# MEDIDOR_MTE.net
KiCad netlist of a schematic drawn in EAGLE
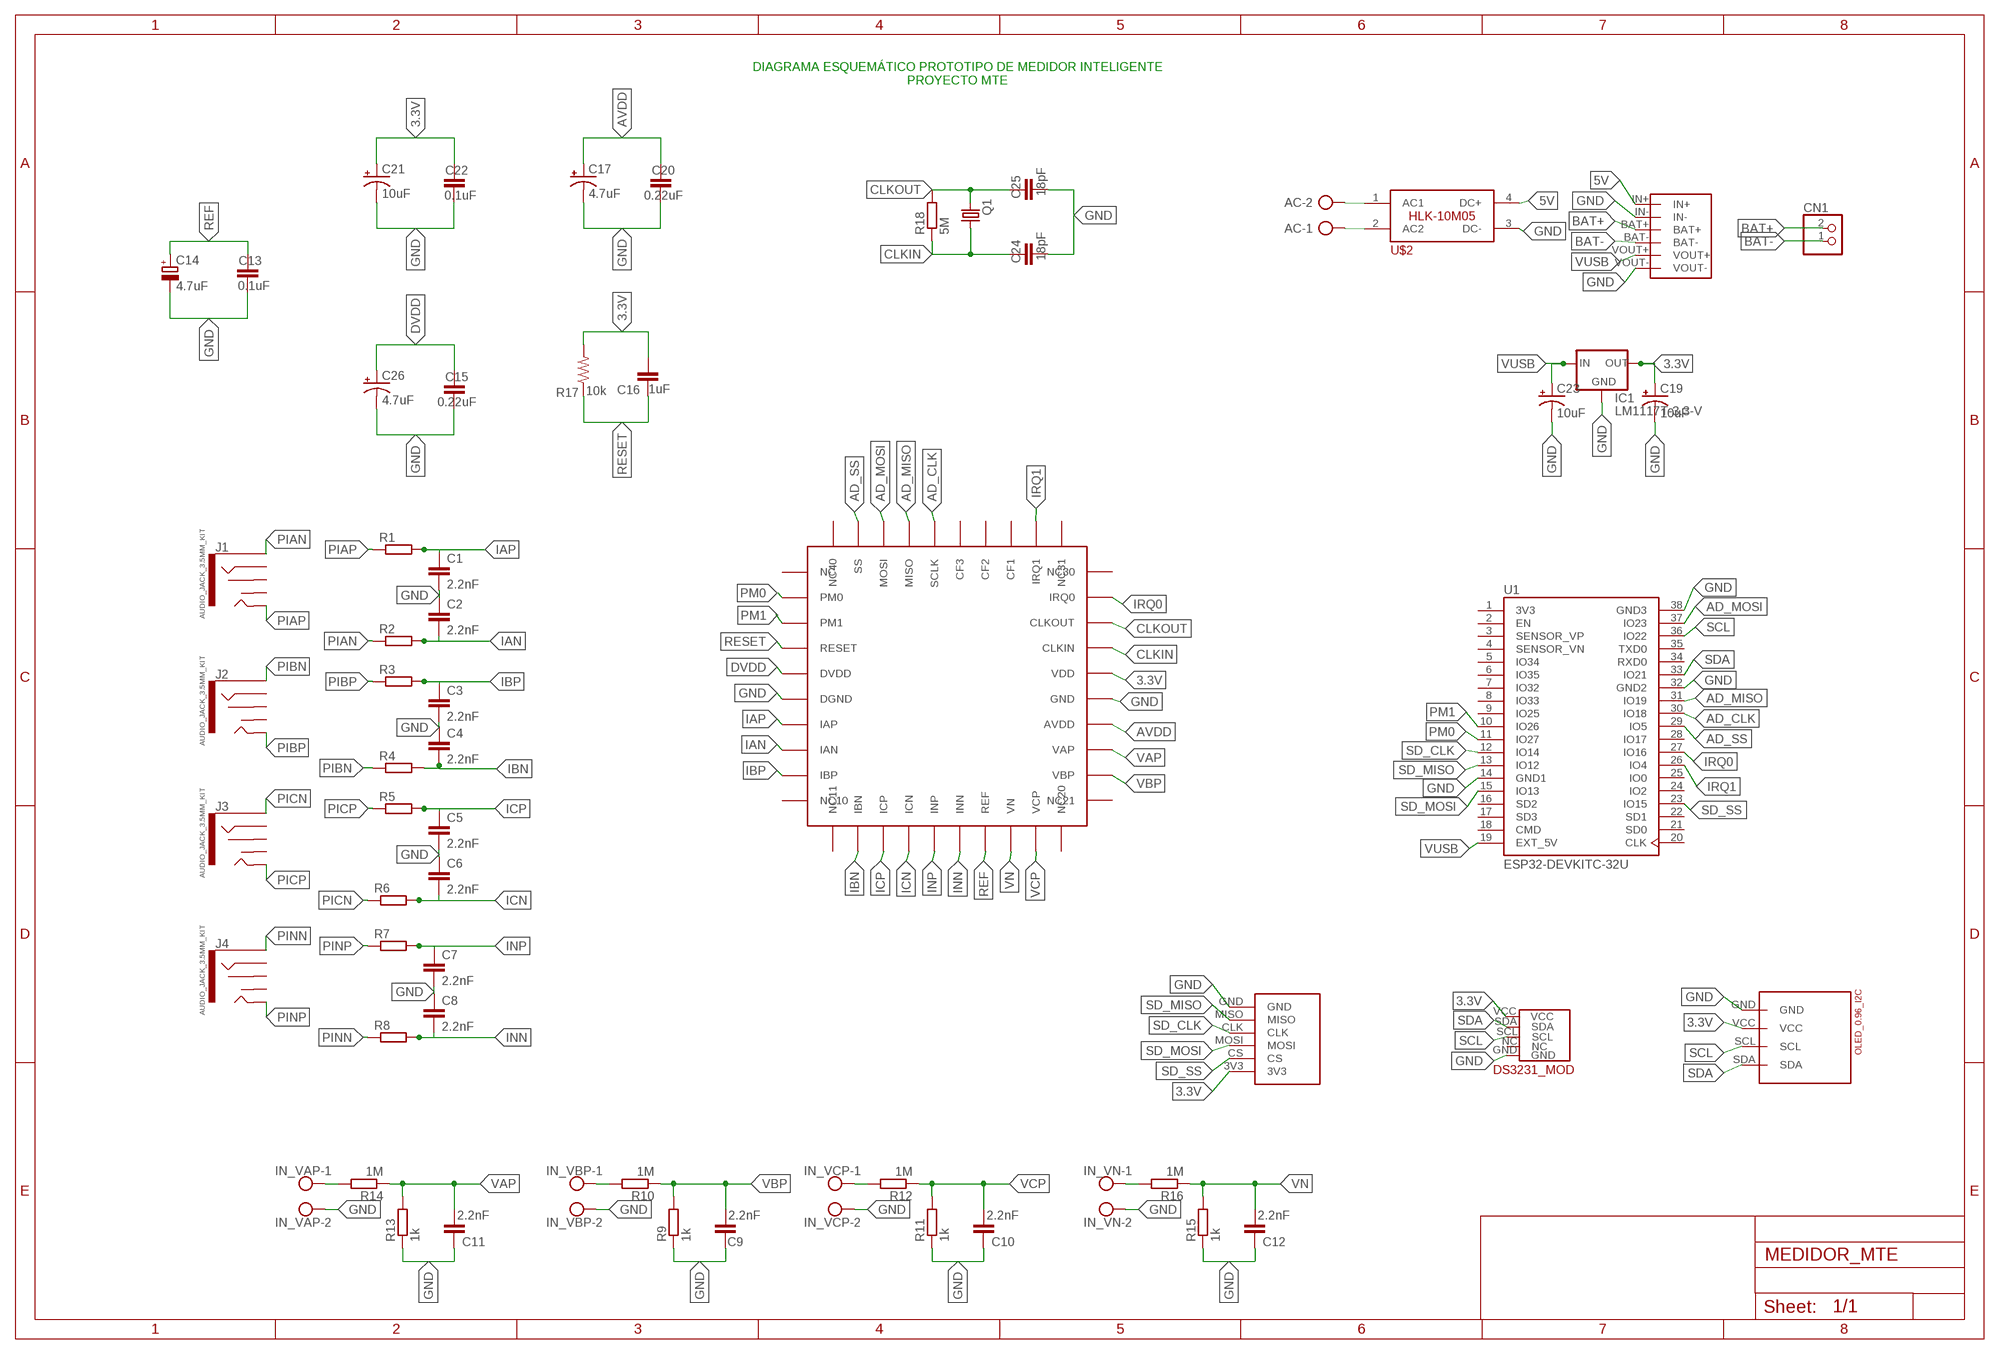
[diagram p0: schematic, sheet 1]

(export (version "E")
  (design (tool "Eeschema 10.0.6"))
  (components
    (comp (ref "AC")
      (value "AK500/2")
      (footprint "eagle-import:AK500_2")
      (libsource (lib "eagle-import") (part "AK500/2"))
    )
    (comp (ref "C1")
      (value "2.2nF")
      (footprint "eagle-import:C025-025X050")
      (libsource (lib "eagle-import") (part "C-EU025-025X050"))
    )
    (comp (ref "C2")
      (value "2.2nF")
      (footprint "eagle-import:C025-025X050")
      (libsource (lib "eagle-import") (part "C-EU025-025X050"))
    )
    (comp (ref "C3")
      (value "2.2nF")
      (footprint "eagle-import:C025-025X050")
      (libsource (lib "eagle-import") (part "C-EU025-025X050"))
    )
    (comp (ref "C4")
      (value "2.2nF")
      (footprint "eagle-import:C025-025X050")
      (libsource (lib "eagle-import") (part "C-EU025-025X050"))
    )
    (comp (ref "C5")
      (value "2.2nF")
      (footprint "eagle-import:C025-025X050")
      (libsource (lib "eagle-import") (part "C-EU025-025X050"))
    )
    (comp (ref "C6")
      (value "2.2nF")
      (footprint "eagle-import:C025-025X050")
      (libsource (lib "eagle-import") (part "C-EU025-025X050"))
    )
    (comp (ref "C7")
      (value "2.2nF")
      (footprint "eagle-import:C025-025X050")
      (libsource (lib "eagle-import") (part "C-EU025-025X050"))
    )
    (comp (ref "C8")
      (value "2.2nF")
      (footprint "eagle-import:C025-025X050")
      (libsource (lib "eagle-import") (part "C-EU025-025X050"))
    )
    (comp (ref "C9")
      (value "2.2nF")
      (footprint "eagle-import:C025-025X050")
      (libsource (lib "eagle-import") (part "C-EU025-025X050"))
    )
    (comp (ref "C10")
      (value "2.2nF")
      (footprint "eagle-import:C025-025X050")
      (libsource (lib "eagle-import") (part "C-EU025-025X050"))
    )
    (comp (ref "C11")
      (value "2.2nF")
      (footprint "eagle-import:C025-025X050")
      (libsource (lib "eagle-import") (part "C-EU025-025X050"))
    )
    (comp (ref "C12")
      (value "2.2nF")
      (footprint "eagle-import:C025-025X050")
      (libsource (lib "eagle-import") (part "C-EU025-025X050"))
    )
    (comp (ref "C13")
      (value "0.1uF")
      (footprint "eagle-import:C025-025X050")
      (libsource (lib "eagle-import") (part "C-EU025-025X050"))
    )
    (comp (ref "C14")
      (value "4.7uF")
      (footprint "eagle-import:E3,5-8")
      (libsource (lib "eagle-import") (part "CPOL-EUE3.5-8"))
    )
    (comp (ref "C15")
      (value "0.22uF")
      (footprint "eagle-import:C025-025X050")
      (libsource (lib "eagle-import") (part "C-EU025-025X050"))
    )
    (comp (ref "C16")
      (value "1uF")
      (footprint "eagle-import:C025-025X050")
      (libsource (lib "eagle-import") (part "C-EU025-025X050"))
    )
    (comp (ref "C17")
      (value "4.7uF")
      (footprint "eagle-import:E3,5-8")
      (libsource (lib "eagle-import") (part "CPOL-USE3.5-8"))
    )
    (comp (ref "C19")
      (value "10uF")
      (footprint "eagle-import:CPOL-RADIAL-2.5MM-5MM")
      (libsource (lib "eagle-import") (part "10UF-POLAR-RADIAL-2.5MM-25V-20%"))
    )
    (comp (ref "C20")
      (value "0.22uF")
      (footprint "eagle-import:C025-025X050")
      (libsource (lib "eagle-import") (part "C-EU025-025X050"))
    )
    (comp (ref "C21")
      (value "10uF")
      (footprint "eagle-import:E3,5-8")
      (libsource (lib "eagle-import") (part "CPOL-USE3.5-8"))
    )
    (comp (ref "C22")
      (value "0.1uF")
      (footprint "eagle-import:C025-025X050")
      (libsource (lib "eagle-import") (part "C-EU025-025X050"))
    )
    (comp (ref "C23")
      (value "10uF")
      (footprint "eagle-import:CPOL-RADIAL-2.5MM-5MM")
      (libsource (lib "eagle-import") (part "10UF-POLAR-RADIAL-2.5MM-25V-20%"))
    )
    (comp (ref "C24")
      (value "18pF")
      (footprint "eagle-import:C025-025X050")
      (libsource (lib "eagle-import") (part "C-EU025-025X050"))
    )
    (comp (ref "C25")
      (value "18pF")
      (footprint "eagle-import:C025-025X050")
      (libsource (lib "eagle-import") (part "C-EU025-025X050"))
    )
    (comp (ref "C26")
      (value "4.7uF")
      (footprint "eagle-import:E3,5-8")
      (libsource (lib "eagle-import") (part "CPOL-USE3.5-8"))
    )
    (comp (ref "CN1")
      (value "JST_2PIN-THM")
      (footprint "eagle-import:JST-PH-2-THM")
      (libsource (lib "eagle-import") (part "JST_2PIN-THM"))
    )
    (comp (ref "IC1")
      (value "LM1117T-3.3-V")
      (footprint "eagle-import:TO220V")
      (libsource (lib "eagle-import") (part "LM1117T--V3.3"))
    )
    (comp (ref "IN_VAP")
      (value "AK500/2")
      (footprint "eagle-import:AK500_2")
      (libsource (lib "eagle-import") (part "AK500/2"))
    )
    (comp (ref "IN_VBP")
      (value "AK500/2")
      (footprint "eagle-import:AK500_2")
      (libsource (lib "eagle-import") (part "AK500/2"))
    )
    (comp (ref "IN_VCP")
      (value "AK500/2")
      (footprint "eagle-import:AK500_2")
      (libsource (lib "eagle-import") (part "AK500/2"))
    )
    (comp (ref "IN_VN")
      (value "AK500/2")
      (footprint "eagle-import:AK500_2")
      (libsource (lib "eagle-import") (part "AK500/2"))
    )
    (comp (ref "J1")
      (value "AUDIO_JACK_3.5MM_KIT")
      (footprint "eagle-import:AUDIO-JACK-KIT")
      (libsource (lib "eagle-import") (part "AUDIO_JACK_3.5MM_KIT"))
    )
    (comp (ref "J2")
      (value "AUDIO_JACK_3.5MM_KIT")
      (footprint "eagle-import:AUDIO-JACK-KIT")
      (libsource (lib "eagle-import") (part "AUDIO_JACK_3.5MM_KIT"))
    )
    (comp (ref "J3")
      (value "AUDIO_JACK_3.5MM_KIT")
      (footprint "eagle-import:AUDIO-JACK-KIT")
      (libsource (lib "eagle-import") (part "AUDIO_JACK_3.5MM_KIT"))
    )
    (comp (ref "J4")
      (value "AUDIO_JACK_3.5MM_KIT")
      (footprint "eagle-import:AUDIO-JACK-KIT")
      (libsource (lib "eagle-import") (part "AUDIO_JACK_3.5MM_KIT"))
    )
    (comp (ref "Q1")
      (value "CRYSTALHC49S")
      (footprint "eagle-import:HC49_S")
      (libsource (lib "eagle-import") (part "CRYSTALHC49S"))
    )
    (comp (ref "R1")
      (value "R-EU_0207/12")
      (footprint "eagle-import:0207_12")
      (libsource (lib "eagle-import") (part "R-EU_0207/12"))
    )
    (comp (ref "R2")
      (value "R-EU_0207/12")
      (footprint "eagle-import:0207_12")
      (libsource (lib "eagle-import") (part "R-EU_0207/12"))
    )
    (comp (ref "R3")
      (value "R-EU_0207/12")
      (footprint "eagle-import:0207_12")
      (libsource (lib "eagle-import") (part "R-EU_0207/12"))
    )
    (comp (ref "R4")
      (value "R-EU_0207/12")
      (footprint "eagle-import:0207_12")
      (libsource (lib "eagle-import") (part "R-EU_0207/12"))
    )
    (comp (ref "R5")
      (value "R-EU_0207/12")
      (footprint "eagle-import:0207_12")
      (libsource (lib "eagle-import") (part "R-EU_0207/12"))
    )
    (comp (ref "R6")
      (value "R-EU_0207/12")
      (footprint "eagle-import:0207_12")
      (libsource (lib "eagle-import") (part "R-EU_0207/12"))
    )
    (comp (ref "R7")
      (value "R-EU_0207/12")
      (footprint "eagle-import:0207_12")
      (libsource (lib "eagle-import") (part "R-EU_0207/12"))
    )
    (comp (ref "R8")
      (value "R-EU_0207/12")
      (footprint "eagle-import:0207_12")
      (libsource (lib "eagle-import") (part "R-EU_0207/12"))
    )
    (comp (ref "R9")
      (value "1k")
      (footprint "eagle-import:0207_12")
      (libsource (lib "eagle-import") (part "rcl_v2_30891193_R-EU_0207/12"))
    )
    (comp (ref "R10")
      (value "1M")
      (footprint "eagle-import:0207_12")
      (libsource (lib "eagle-import") (part "rcl_v2_30891193_R-EU_0207/12"))
    )
    (comp (ref "R11")
      (value "1k")
      (footprint "eagle-import:0207_12")
      (libsource (lib "eagle-import") (part "rcl_v2_30891193_R-EU_0207/12"))
    )
    (comp (ref "R12")
      (value "1M")
      (footprint "eagle-import:0207_12")
      (libsource (lib "eagle-import") (part "rcl_v2_30891193_R-EU_0207/12"))
    )
    (comp (ref "R13")
      (value "1k")
      (footprint "eagle-import:0207_12")
      (libsource (lib "eagle-import") (part "rcl_v2_30891193_R-EU_0207/12"))
    )
    (comp (ref "R14")
      (value "1M")
      (footprint "eagle-import:0207_12")
      (libsource (lib "eagle-import") (part "rcl_v2_30891193_R-EU_0207/12"))
    )
    (comp (ref "R15")
      (value "1k")
      (footprint "eagle-import:0207_12")
      (libsource (lib "eagle-import") (part "rcl_v2_30891193_R-EU_0207/12"))
    )
    (comp (ref "R16")
      (value "1M")
      (footprint "eagle-import:0207_12")
      (libsource (lib "eagle-import") (part "rcl_v2_30891193_R-EU_0207/12"))
    )
    (comp (ref "R17")
      (value "10k")
      (footprint "eagle-import:0207_12")
      (libsource (lib "eagle-import") (part "R-US_0207/12"))
    )
    (comp (ref "R18")
      (value "5M")
      (footprint "eagle-import:0207_12")
      (libsource (lib "eagle-import") (part "rcl_v2_30891193_R-EU_0207/12"))
    )
    (comp (ref "U$2")
      (value "HLK-10M05")
      (footprint "eagle-import:HLK-10M05")
      (fields (field (name "MF") "Hi-link") (field (name "MP") "hlk-pm01"))
      (libsource (lib "eagle-import") (part "HLK-10M05"))
    )
    (comp (ref "U$3")
      (value "J5019_UPS")
      (footprint "eagle-import:J5019_UPS")
      (libsource (lib "eagle-import") (part "J5019_UPS"))
    )
    (comp (ref "U$4")
      (value "OLED_I2C_096")
      (footprint "eagle-import:OLED_096_I2C")
      (libsource (lib "eagle-import") (part "OLED_I2C_096"))
    )
    (comp (ref "U$5")
      (value "MODULO_MSD2")
      (footprint "eagle-import:MICROSD-BREAKOUT")
      (libsource (lib "eagle-import") (part "MODULO_MSD2"))
    )
    (comp (ref "U$6")
      (value "DS3231_MOD")
      (footprint "eagle-import:DS3231_MOD")
      (libsource (lib "eagle-import") (part "DS3231_MOD"))
    )
    (comp (ref "U1")
      (value "ESP32-DEVKITC-32U")
      (footprint "eagle-import:MODULE_ESP32-DEVKITC-32U")
      (fields (field (name "MF") "Espressif Systems"))
      (libsource (lib "eagle-import") (part "ESP32-DEVKITC-32U"))
    )
    (comp (ref "U2")
      (value "ADE7880")
      (footprint "eagle-import:ADE7880_HDER")
      (libsource (lib "eagle-import") (part "ADE7880"))
    )
  )
  (nets
    (net (code "1") (name "/3V3") (class "Default")
      (node (ref "U1") (pin "1") (pinfunction "3V3_1") (pintype "power_in"))
    )
    (net (code "2") (name "3.3V") (class "Default")
      (node (ref "C16") (pin "2") (pinfunction "2_2") (pintype "passive"))
      (node (ref "C19") (pin "1") (pinfunction "+_1") (pintype "passive"))
      (node (ref "C21") (pin "+") (pinfunction "+_+") (pintype "passive"))
      (node (ref "C22") (pin "2") (pinfunction "2_2") (pintype "passive"))
      (node (ref "IC1") (pin "2") (pinfunction "OUT_2") (pintype "passive"))
      (node (ref "R17") (pin "2") (pinfunction "2_2") (pintype "passive"))
      (node (ref "U$4") (pin "VCC") (pinfunction "VCC_VCC") (pintype "power_in"))
      (node (ref "U$5") (pin "3V3") (pinfunction "3V3_3V3") (pintype "bidirectional"))
      (node (ref "U$6") (pin "VCC") (pinfunction "VCC_VCC") (pintype "bidirectional"))
      (node (ref "U2") (pin "PIN26") (pinfunction "VDD_PIN26") (pintype "power_in"))
    )
    (net (code "3") (name "5V") (class "Default")
      (node (ref "U$2") (pin "4") (pinfunction "DC+_4") (pintype "power_in"))
      (node (ref "U$3") (pin "IN+") (pinfunction "IN+_IN+") (pintype "bidirectional"))
    )
    (net (code "4") (name "AD_CLK") (class "Default")
      (node (ref "U1") (pin "30") (pinfunction "IO18_30") (pintype "bidirectional"))
      (node (ref "U2") (pin "PIN36") (pinfunction "SCLK_PIN36") (pintype "bidirectional"))
    )
    (net (code "5") (name "AD_MISO") (class "Default")
      (node (ref "U1") (pin "31") (pinfunction "IO19_31") (pintype "bidirectional"))
      (node (ref "U2") (pin "PIN37") (pinfunction "MISO_PIN37") (pintype "bidirectional"))
    )
    (net (code "6") (name "AD_MOSI") (class "Default")
      (node (ref "U1") (pin "37") (pinfunction "IO23_37") (pintype "bidirectional"))
      (node (ref "U2") (pin "PIN38") (pinfunction "MOSI_PIN38") (pintype "bidirectional"))
    )
    (net (code "7") (name "AD_SS") (class "Default")
      (node (ref "U1") (pin "29") (pinfunction "IO5_29") (pintype "bidirectional"))
      (node (ref "U2") (pin "PIN39") (pinfunction "SS_PIN39") (pintype "input"))
    )
    (net (code "8") (name "AVDD") (class "Default")
      (node (ref "C17") (pin "+") (pinfunction "+_+") (pintype "passive"))
      (node (ref "C20") (pin "2") (pinfunction "2_2") (pintype "passive"))
      (node (ref "U2") (pin "PIN24") (pinfunction "AVDD_PIN24") (pintype "power_in"))
    )
    (net (code "9") (name "BAT+") (class "Default")
      (node (ref "CN1") (pin "2") (pinfunction "1_2") (pintype "passive"))
      (node (ref "U$3") (pin "BAT+") (pinfunction "BAT+_BAT+") (pintype "bidirectional"))
    )
    (net (code "10") (name "BAT-") (class "Default")
      (node (ref "CN1") (pin "1") (pinfunction "2_1") (pintype "passive"))
      (node (ref "U$3") (pin "BAT-") (pinfunction "BAT-_BAT-") (pintype "bidirectional"))
    )
    (net (code "11") (name "CLKIN") (class "Default")
      (node (ref "C24") (pin "2") (pinfunction "2_2") (pintype "passive"))
      (node (ref "Q1") (pin "1") (pinfunction "1_1") (pintype "passive"))
      (node (ref "R18") (pin "1") (pinfunction "1_1") (pintype "passive"))
      (node (ref "U2") (pin "PIN27") (pinfunction "CLKIN_PIN27") (pintype "input"))
    )
    (net (code "12") (name "CLKOUT") (class "Default")
      (node (ref "C25") (pin "2") (pinfunction "2_2") (pintype "passive"))
      (node (ref "Q1") (pin "2") (pinfunction "2_2") (pintype "passive"))
      (node (ref "R18") (pin "2") (pinfunction "2_2") (pintype "passive"))
      (node (ref "U2") (pin "PIN28") (pinfunction "CLKOUT_PIN28") (pintype "output"))
    )
    (net (code "13") (name "DVDD") (class "Default")
      (node (ref "C15") (pin "2") (pinfunction "2_2") (pintype "passive"))
      (node (ref "C26") (pin "+") (pinfunction "+_+") (pintype "passive"))
      (node (ref "U2") (pin "PIN5") (pinfunction "DVDD_PIN5") (pintype "power_in"))
    )
    (net (code "14") (name "GND") (class "Default")
      (node (ref "C1") (pin "2") (pinfunction "2_2") (pintype "passive"))
      (node (ref "C10") (pin "1") (pinfunction "1_1") (pintype "passive"))
      (node (ref "C11") (pin "1") (pinfunction "1_1") (pintype "passive"))
      (node (ref "C12") (pin "1") (pinfunction "1_1") (pintype "passive"))
      (node (ref "C13") (pin "1") (pinfunction "1_1") (pintype "passive"))
      (node (ref "C14") (pin "-") (pinfunction "-_-") (pintype "passive"))
      (node (ref "C15") (pin "1") (pinfunction "1_1") (pintype "passive"))
      (node (ref "C17") (pin "-") (pinfunction "-_-") (pintype "passive"))
      (node (ref "C19") (pin "2") (pinfunction "-_2") (pintype "passive"))
      (node (ref "C2") (pin "1") (pinfunction "1_1") (pintype "passive"))
      (node (ref "C20") (pin "1") (pinfunction "1_1") (pintype "passive"))
      (node (ref "C21") (pin "-") (pinfunction "-_-") (pintype "passive"))
      (node (ref "C22") (pin "1") (pinfunction "1_1") (pintype "passive"))
      (node (ref "C23") (pin "2") (pinfunction "-_2") (pintype "passive"))
      (node (ref "C24") (pin "1") (pinfunction "1_1") (pintype "passive"))
      (node (ref "C25") (pin "1") (pinfunction "1_1") (pintype "passive"))
      (node (ref "C26") (pin "-") (pinfunction "-_-") (pintype "passive"))
      (node (ref "C3") (pin "2") (pinfunction "2_2") (pintype "passive"))
      (node (ref "C4") (pin "1") (pinfunction "1_1") (pintype "passive"))
      (node (ref "C5") (pin "2") (pinfunction "2_2") (pintype "passive"))
      (node (ref "C6") (pin "1") (pinfunction "1_1") (pintype "passive"))
      (node (ref "C7") (pin "2") (pinfunction "2_2") (pintype "passive"))
      (node (ref "C8") (pin "1") (pinfunction "1_1") (pintype "passive"))
      (node (ref "C9") (pin "1") (pinfunction "1_1") (pintype "passive"))
      (node (ref "IC1") (pin "1") (pinfunction "GND_1") (pintype "input"))
      (node (ref "IN_VAP") (pin "2") (pinfunction "KL_2") (pintype "passive"))
      (node (ref "IN_VBP") (pin "2") (pinfunction "KL_2") (pintype "passive"))
      (node (ref "IN_VCP") (pin "2") (pinfunction "KL_2") (pintype "passive"))
      (node (ref "IN_VN") (pin "2") (pinfunction "KL_2") (pintype "passive"))
      (node (ref "R11") (pin "1") (pinfunction "1_1") (pintype "passive"))
      (node (ref "R13") (pin "1") (pinfunction "1_1") (pintype "passive"))
      (node (ref "R15") (pin "1") (pinfunction "1_1") (pintype "passive"))
      (node (ref "R9") (pin "1") (pinfunction "1_1") (pintype "passive"))
      (node (ref "U$2") (pin "3") (pinfunction "DC-_3") (pintype "power_in"))
      (node (ref "U$3") (pin "IN-") (pinfunction "IN-_IN-") (pintype "bidirectional"))
      (node (ref "U$3") (pin "VOUT-") (pinfunction "VOUT-_VOUT-") (pintype "bidirectional"))
      (node (ref "U$4") (pin "GND") (pinfunction "GND_GND") (pintype "power_in"))
      (node (ref "U$5") (pin "GND") (pinfunction "GND_GND") (pintype "bidirectional"))
      (node (ref "U$6") (pin "GND") (pinfunction "GND_GND") (pintype "bidirectional"))
      (node (ref "U1") (pin "14") (pinfunction "GND1_14") (pintype "power_in"))
      (node (ref "U1") (pin "32") (pinfunction "GND2_32") (pintype "power_in"))
      (node (ref "U1") (pin "38") (pinfunction "GND3_38") (pintype "power_in"))
      (node (ref "U2") (pin "PIN25") (pinfunction "GND_PIN25") (pintype "power_in"))
      (node (ref "U2") (pin "PIN6") (pinfunction "DGND_PIN6") (pintype "power_in"))
    )
    (net (code "15") (name "IAN") (class "Default")
      (node (ref "C2") (pin "2") (pinfunction "2_2") (pintype "passive"))
      (node (ref "R2") (pin "2") (pinfunction "2_2") (pintype "passive"))
      (node (ref "U2") (pin "PIN8") (pinfunction "IAN_PIN8") (pintype "input"))
    )
    (net (code "16") (name "IAP") (class "Default")
      (node (ref "C1") (pin "1") (pinfunction "1_1") (pintype "passive"))
      (node (ref "R1") (pin "2") (pinfunction "2_2") (pintype "passive"))
      (node (ref "U2") (pin "PIN7") (pinfunction "IAP_PIN7") (pintype "input"))
    )
    (net (code "17") (name "IBN") (class "Default")
      (node (ref "C4") (pin "2") (pinfunction "2_2") (pintype "passive"))
      (node (ref "R4") (pin "2") (pinfunction "2_2") (pintype "passive"))
      (node (ref "U2") (pin "PIN12") (pinfunction "IBN_PIN12") (pintype "input"))
    )
    (net (code "18") (name "IBP") (class "Default")
      (node (ref "C3") (pin "1") (pinfunction "1_1") (pintype "passive"))
      (node (ref "R3") (pin "2") (pinfunction "2_2") (pintype "passive"))
      (node (ref "U2") (pin "PIN9") (pinfunction "IBP_PIN9") (pintype "input"))
    )
    (net (code "19") (name "ICN") (class "Default")
      (node (ref "C6") (pin "2") (pinfunction "2_2") (pintype "passive"))
      (node (ref "R6") (pin "2") (pinfunction "2_2") (pintype "passive"))
      (node (ref "U2") (pin "PIN14") (pinfunction "ICN_PIN14") (pintype "input"))
    )
    (net (code "20") (name "ICP") (class "Default")
      (node (ref "C5") (pin "1") (pinfunction "1_1") (pintype "passive"))
      (node (ref "R5") (pin "2") (pinfunction "2_2") (pintype "passive"))
      (node (ref "U2") (pin "PIN13") (pinfunction "ICP_PIN13") (pintype "input"))
    )
    (net (code "21") (name "INN") (class "Default")
      (node (ref "C8") (pin "2") (pinfunction "2_2") (pintype "passive"))
      (node (ref "R8") (pin "2") (pinfunction "2_2") (pintype "passive"))
      (node (ref "U2") (pin "PIN16") (pinfunction "INN_PIN16") (pintype "input"))
    )
    (net (code "22") (name "INP") (class "Default")
      (node (ref "C7") (pin "1") (pinfunction "1_1") (pintype "passive"))
      (node (ref "R7") (pin "2") (pinfunction "2_2") (pintype "passive"))
      (node (ref "U2") (pin "PIN15") (pinfunction "INP_PIN15") (pintype "input"))
    )
    (net (code "23") (name "IRQ0") (class "Default")
      (node (ref "U1") (pin "27") (pinfunction "IO16_27") (pintype "bidirectional"))
      (node (ref "U2") (pin "PIN29") (pinfunction "IRQ0_PIN29") (pintype "output"))
    )
    (net (code "24") (name "IRQ1") (class "Default")
      (node (ref "U1") (pin "26") (pinfunction "IO4_26") (pintype "bidirectional"))
      (node (ref "U2") (pin "PIN32") (pinfunction "IRQ1_PIN32") (pintype "output"))
    )
    (net (code "25") (name "Net-(ACA-KL)") (class "Default")
      (node (ref "AC") (pin "1") (pinfunction "KL_1") (pintype "passive"))
      (node (ref "U$2") (pin "2") (pinfunction "AC2_2") (pintype "power_in"))
    )
    (net (code "26") (name "Net-(ACB-KL)") (class "Default")
      (node (ref "AC") (pin "2") (pinfunction "KL_2") (pintype "passive"))
      (node (ref "U$2") (pin "1") (pinfunction "AC1_1") (pintype "power_in"))
    )
    (net (code "27") (name "Net-(IN_VAPA-KL)") (class "Default")
      (node (ref "IN_VAP") (pin "1") (pinfunction "KL_1") (pintype "passive"))
      (node (ref "R14") (pin "2") (pinfunction "2_2") (pintype "passive"))
    )
    (net (code "28") (name "Net-(IN_VBPA-KL)") (class "Default")
      (node (ref "IN_VBP") (pin "1") (pinfunction "KL_1") (pintype "passive"))
      (node (ref "R10") (pin "2") (pinfunction "2_2") (pintype "passive"))
    )
    (net (code "29") (name "Net-(IN_VCPA-KL)") (class "Default")
      (node (ref "IN_VCP") (pin "1") (pinfunction "KL_1") (pintype "passive"))
      (node (ref "R12") (pin "2") (pinfunction "2_2") (pintype "passive"))
    )
    (net (code "30") (name "Net-(IN_VNA-KL)") (class "Default")
      (node (ref "IN_VN") (pin "1") (pinfunction "KL_1") (pintype "passive"))
      (node (ref "R16") (pin "2") (pinfunction "2_2") (pintype "passive"))
    )
    (net (code "31") (name "PIAN") (class "Default")
      (node (ref "J1") (pin "SLEEVE") (pinfunction "SLEEVE_SLEEVE") (pintype "bidirectional"))
      (node (ref "R2") (pin "1") (pinfunction "1_1") (pintype "passive"))
    )
    (net (code "32") (name "PIAP") (class "Default")
      (node (ref "J1") (pin "TIP") (pinfunction "TIP_TIP") (pintype "bidirectional"))
      (node (ref "R1") (pin "1") (pinfunction "1_1") (pintype "passive"))
    )
    (net (code "33") (name "PIBN") (class "Default")
      (node (ref "J2") (pin "SLEEVE") (pinfunction "SLEEVE_SLEEVE") (pintype "bidirectional"))
      (node (ref "R4") (pin "1") (pinfunction "1_1") (pintype "passive"))
    )
    (net (code "34") (name "PIBP") (class "Default")
      (node (ref "J2") (pin "TIP") (pinfunction "TIP_TIP") (pintype "bidirectional"))
      (node (ref "R3") (pin "1") (pinfunction "1_1") (pintype "passive"))
    )
    (net (code "35") (name "PICN") (class "Default")
      (node (ref "J3") (pin "SLEEVE") (pinfunction "SLEEVE_SLEEVE") (pintype "bidirectional"))
      (node (ref "R6") (pin "1") (pinfunction "1_1") (pintype "passive"))
    )
    (net (code "36") (name "PICP") (class "Default")
      (node (ref "J3") (pin "TIP") (pinfunction "TIP_TIP") (pintype "bidirectional"))
      (node (ref "R5") (pin "1") (pinfunction "1_1") (pintype "passive"))
    )
    (net (code "37") (name "PINN") (class "Default")
      (node (ref "J4") (pin "SLEEVE") (pinfunction "SLEEVE_SLEEVE") (pintype "bidirectional"))
      (node (ref "R8") (pin "1") (pinfunction "1_1") (pintype "passive"))
    )
    (net (code "38") (name "PINP") (class "Default")
      (node (ref "J4") (pin "TIP") (pinfunction "TIP_TIP") (pintype "bidirectional"))
      (node (ref "R7") (pin "1") (pinfunction "1_1") (pintype "passive"))
    )
    (net (code "39") (name "PM0") (class "Default")
      (node (ref "U1") (pin "11") (pinfunction "IO27_11") (pintype "bidirectional"))
      (node (ref "U2") (pin "PIN2") (pinfunction "PM0_PIN2") (pintype "input"))
    )
    (net (code "40") (name "PM1") (class "Default")
      (node (ref "U1") (pin "10") (pinfunction "IO26_10") (pintype "bidirectional"))
      (node (ref "U2") (pin "PIN3") (pinfunction "PM1_PIN3") (pintype "input"))
    )
    (net (code "41") (name "REF") (class "Default")
      (node (ref "C13") (pin "2") (pinfunction "2_2") (pintype "passive"))
      (node (ref "C14") (pin "+") (pinfunction "+_+") (pintype "passive"))
      (node (ref "U2") (pin "PIN17") (pinfunction "REF_PIN17") (pintype "input"))
    )
    (net (code "42") (name "RESET") (class "Default")
      (node (ref "C16") (pin "1") (pinfunction "1_1") (pintype "passive"))
      (node (ref "R17") (pin "1") (pinfunction "1_1") (pintype "passive"))
      (node (ref "U2") (pin "PIN4") (pinfunction "RESET_PIN4") (pintype "input"))
    )
    (net (code "43") (name "SCL") (class "Default")
      (node (ref "U$4") (pin "SCL") (pinfunction "SCL_SCL") (pintype "bidirectional"))
      (node (ref "U$6") (pin "SCL") (pinfunction "SCL_SCL") (pintype "bidirectional"))
      (node (ref "U1") (pin "36") (pinfunction "IO22_36") (pintype "bidirectional"))
    )
    (net (code "44") (name "SDA") (class "Default")
      (node (ref "U$4") (pin "SDA") (pinfunction "SDA_SDA") (pintype "bidirectional"))
      (node (ref "U$6") (pin "SDA") (pinfunction "SDA_SDA") (pintype "bidirectional"))
      (node (ref "U1") (pin "33") (pinfunction "IO21_33") (pintype "bidirectional"))
    )
    (net (code "45") (name "SD_CLK") (class "Default")
      (node (ref "U$5") (pin "CLK") (pinfunction "CLK_CLK") (pintype "bidirectional"))
      (node (ref "U1") (pin "12") (pinfunction "IO14_12") (pintype "bidirectional"))
    )
    (net (code "46") (name "SD_MISO") (class "Default")
      (node (ref "U$5") (pin "MISO") (pinfunction "MISO_MISO") (pintype "bidirectional"))
      (node (ref "U1") (pin "13") (pinfunction "IO12_13") (pintype "bidirectional"))
    )
    (net (code "47") (name "SD_MOSI") (class "Default")
      (node (ref "U$5") (pin "MOSI") (pinfunction "MOSI_MOSI") (pintype "bidirectional"))
      (node (ref "U1") (pin "15") (pinfunction "IO13_15") (pintype "bidirectional"))
    )
    (net (code "48") (name "SD_SS") (class "Default")
      (node (ref "U$5") (pin "CS") (pinfunction "CS_CS") (pintype "bidirectional"))
      (node (ref "U1") (pin "23") (pinfunction "IO15_23") (pintype "bidirectional"))
    )
    (net (code "49") (name "VAP") (class "Default")
      (node (ref "C11") (pin "2") (pinfunction "2_2") (pintype "passive"))
      (node (ref "R13") (pin "2") (pinfunction "2_2") (pintype "passive"))
      (node (ref "R14") (pin "1") (pinfunction "1_1") (pintype "passive"))
      (node (ref "U2") (pin "PIN23") (pinfunction "VAP_PIN23") (pintype "input"))
    )
    (net (code "50") (name "VBP") (class "Default")
      (node (ref "C9") (pin "2") (pinfunction "2_2") (pintype "passive"))
      (node (ref "R10") (pin "1") (pinfunction "1_1") (pintype "passive"))
      (node (ref "R9") (pin "2") (pinfunction "2_2") (pintype "passive"))
      (node (ref "U2") (pin "PIN22") (pinfunction "VBP_PIN22") (pintype "input"))
    )
    (net (code "51") (name "VCP") (class "Default")
      (node (ref "C10") (pin "2") (pinfunction "2_2") (pintype "passive"))
      (node (ref "R11") (pin "2") (pinfunction "2_2") (pintype "passive"))
      (node (ref "R12") (pin "1") (pinfunction "1_1") (pintype "passive"))
      (node (ref "U2") (pin "PIN19") (pinfunction "VCP_PIN19") (pintype "input"))
    )
    (net (code "52") (name "VN") (class "Default")
      (node (ref "C12") (pin "2") (pinfunction "2_2") (pintype "passive"))
      (node (ref "R15") (pin "2") (pinfunction "2_2") (pintype "passive"))
      (node (ref "R16") (pin "1") (pinfunction "1_1") (pintype "passive"))
      (node (ref "U2") (pin "PIN18") (pinfunction "VN_PIN18") (pintype "input"))
    )
    (net (code "53") (name "VUSB") (class "Default")
      (node (ref "C23") (pin "1") (pinfunction "+_1") (pintype "passive"))
      (node (ref "IC1") (pin "3") (pinfunction "IN_3") (pintype "input"))
      (node (ref "U$3") (pin "VOUT+") (pinfunction "VOUT+_VOUT+") (pintype "bidirectional"))
      (node (ref "U1") (pin "19") (pinfunction "EXT_5V_19") (pintype "power_in"))
    )
    (net (code "54") (name "unconnected-(J1-PadRING)") (class "Default")
      (node (ref "J1") (pin "RING") (pinfunction "RING_RING") (pintype "bidirectional"))
    )
    (net (code "55") (name "unconnected-(J1-PadRSH)") (class "Default")
      (node (ref "J1") (pin "RSH") (pinfunction "RSH_RSH") (pintype "bidirectional"))
    )
    (net (code "56") (name "unconnected-(J1-PadTSH)") (class "Default")
      (node (ref "J1") (pin "TSH") (pinfunction "TSH_TSH") (pintype "bidirectional"))
    )
    (net (code "57") (name "unconnected-(J2-PadRING)") (class "Default")
      (node (ref "J2") (pin "RING") (pinfunction "RING_RING") (pintype "bidirectional"))
    )
    (net (code "58") (name "unconnected-(J2-PadRSH)") (class "Default")
      (node (ref "J2") (pin "RSH") (pinfunction "RSH_RSH") (pintype "bidirectional"))
    )
    (net (code "59") (name "unconnected-(J2-PadTSH)") (class "Default")
      (node (ref "J2") (pin "TSH") (pinfunction "TSH_TSH") (pintype "bidirectional"))
    )
    (net (code "60") (name "unconnected-(J3-PadRING)") (class "Default")
      (node (ref "J3") (pin "RING") (pinfunction "RING_RING") (pintype "bidirectional"))
    )
    (net (code "61") (name "unconnected-(J3-PadRSH)") (class "Default")
      (node (ref "J3") (pin "RSH") (pinfunction "RSH_RSH") (pintype "bidirectional"))
    )
    (net (code "62") (name "unconnected-(J3-PadTSH)") (class "Default")
      (node (ref "J3") (pin "TSH") (pinfunction "TSH_TSH") (pintype "bidirectional"))
    )
    (net (code "63") (name "unconnected-(J4-PadRING)") (class "Default")
      (node (ref "J4") (pin "RING") (pinfunction "RING_RING") (pintype "bidirectional"))
    )
    (net (code "64") (name "unconnected-(J4-PadRSH)") (class "Default")
      (node (ref "J4") (pin "RSH") (pinfunction "RSH_RSH") (pintype "bidirectional"))
    )
    (net (code "65") (name "unconnected-(J4-PadTSH)") (class "Default")
      (node (ref "J4") (pin "TSH") (pinfunction "TSH_TSH") (pintype "bidirectional"))
    )
    (net (code "66") (name "unconnected-(U$6-PadNC)") (class "Default")
      (node (ref "U$6") (pin "NC") (pinfunction "NC_NC") (pintype "bidirectional"))
    )
    (net (code "67") (name "unconnected-(U1-CLK-Pad20)") (class "Default")
      (node (ref "U1") (pin "20") (pinfunction "CLK_20") (pintype "input"))
    )
    (net (code "68") (name "unconnected-(U1-CMD-Pad18)") (class "Default")
      (node (ref "U1") (pin "18") (pinfunction "CMD_18") (pintype "bidirectional"))
    )
    (net (code "69") (name "unconnected-(U1-EN-Pad2)") (class "Default")
      (node (ref "U1") (pin "2") (pinfunction "EN_2") (pintype "input"))
    )
    (net (code "70") (name "unconnected-(U1-IO0-Pad25)") (class "Default")
      (node (ref "U1") (pin "25") (pinfunction "IO0_25") (pintype "bidirectional"))
    )
    (net (code "71") (name "unconnected-(U1-IO2-Pad24)") (class "Default")
      (node (ref "U1") (pin "24") (pinfunction "IO2_24") (pintype "bidirectional"))
    )
    (net (code "72") (name "unconnected-(U1-IO17-Pad28)") (class "Default")
      (node (ref "U1") (pin "28") (pinfunction "IO17_28") (pintype "bidirectional"))
    )
    (net (code "73") (name "unconnected-(U1-IO25-Pad9)") (class "Default")
      (node (ref "U1") (pin "9") (pinfunction "IO25_9") (pintype "bidirectional"))
    )
    (net (code "74") (name "unconnected-(U1-IO32-Pad7)") (class "Default")
      (node (ref "U1") (pin "7") (pinfunction "IO32_7") (pintype "bidirectional"))
    )
    (net (code "75") (name "unconnected-(U1-IO33-Pad8)") (class "Default")
      (node (ref "U1") (pin "8") (pinfunction "IO33_8") (pintype "bidirectional"))
    )
    (net (code "76") (name "unconnected-(U1-IO34-Pad5)") (class "Default")
      (node (ref "U1") (pin "5") (pinfunction "IO34_5") (pintype "bidirectional"))
    )
    (net (code "77") (name "unconnected-(U1-IO35-Pad6)") (class "Default")
      (node (ref "U1") (pin "6") (pinfunction "IO35_6") (pintype "bidirectional"))
    )
    (net (code "78") (name "unconnected-(U1-RXD0-Pad34)") (class "Default")
      (node (ref "U1") (pin "34") (pinfunction "RXD0_34") (pintype "input"))
    )
    (net (code "79") (name "unconnected-(U1-SD0-Pad21)") (class "Default")
      (node (ref "U1") (pin "21") (pinfunction "SD0_21") (pintype "bidirectional"))
    )
    (net (code "80") (name "unconnected-(U1-SD1-Pad22)") (class "Default")
      (node (ref "U1") (pin "22") (pinfunction "SD1_22") (pintype "bidirectional"))
    )
    (net (code "81") (name "unconnected-(U1-SD2-Pad16)") (class "Default")
      (node (ref "U1") (pin "16") (pinfunction "SD2_16") (pintype "bidirectional"))
    )
    (net (code "82") (name "unconnected-(U1-SD3-Pad17)") (class "Default")
      (node (ref "U1") (pin "17") (pinfunction "SD3_17") (pintype "bidirectional"))
    )
    (net (code "83") (name "unconnected-(U1-SENSOR_VN-Pad4)") (class "Default")
      (node (ref "U1") (pin "4") (pinfunction "SENSOR_VN_4") (pintype "input"))
    )
    (net (code "84") (name "unconnected-(U1-SENSOR_VP-Pad3)") (class "Default")
      (node (ref "U1") (pin "3") (pinfunction "SENSOR_VP_3") (pintype "input"))
    )
    (net (code "85") (name "unconnected-(U1-TXD0-Pad35)") (class "Default")
      (node (ref "U1") (pin "35") (pinfunction "TXD0_35") (pintype "output"))
    )
    (net (code "86") (name "unconnected-(U2-CF1-PadPIN33)") (class "Default")
      (node (ref "U2") (pin "PIN33") (pinfunction "CF1_PIN33") (pintype "bidirectional"))
    )
    (net (code "87") (name "unconnected-(U2-CF2-PadPIN34)") (class "Default")
      (node (ref "U2") (pin "PIN34") (pinfunction "CF2_PIN34") (pintype "bidirectional"))
    )
    (net (code "88") (name "unconnected-(U2-CF3-PadPIN35)") (class "Default")
      (node (ref "U2") (pin "PIN35") (pinfunction "CF3_PIN35") (pintype "bidirectional"))
    )
    (net (code "89") (name "unconnected-(U2-NC-PadPIN1)") (class "Default")
      (node (ref "U2") (pin "PIN1") (pinfunction "NC_PIN1") (pintype "no_connect"))
    )
    (net (code "90") (name "unconnected-(U2-NC10-PadPIN10)") (class "Default")
      (node (ref "U2") (pin "PIN10") (pinfunction "NC10_PIN10") (pintype "no_connect"))
    )
    (net (code "91") (name "unconnected-(U2-NC11-PadPIN11)") (class "Default")
      (node (ref "U2") (pin "PIN11") (pinfunction "NC11_PIN11") (pintype "no_connect"))
    )
    (net (code "92") (name "unconnected-(U2-NC20-PadPIN20)") (class "Default")
      (node (ref "U2") (pin "PIN20") (pinfunction "NC20_PIN20") (pintype "no_connect"))
    )
    (net (code "93") (name "unconnected-(U2-NC21-PadPIN21)") (class "Default")
      (node (ref "U2") (pin "PIN21") (pinfunction "NC21_PIN21") (pintype "no_connect"))
    )
    (net (code "94") (name "unconnected-(U2-NC30-PadPIN30)") (class "Default")
      (node (ref "U2") (pin "PIN30") (pinfunction "NC30_PIN30") (pintype "no_connect"))
    )
    (net (code "95") (name "unconnected-(U2-NC31-PadPIN31)") (class "Default")
      (node (ref "U2") (pin "PIN31") (pinfunction "NC31_PIN31") (pintype "no_connect"))
    )
    (net (code "96") (name "unconnected-(U2-NC40-PadPIN40)") (class "Default")
      (node (ref "U2") (pin "PIN40") (pinfunction "NC40_PIN40") (pintype "no_connect"))
    )
  )
)
